# 2_BLE-T1-matrix.net
KiCad netlist of a schematic drawn in Altium Designer
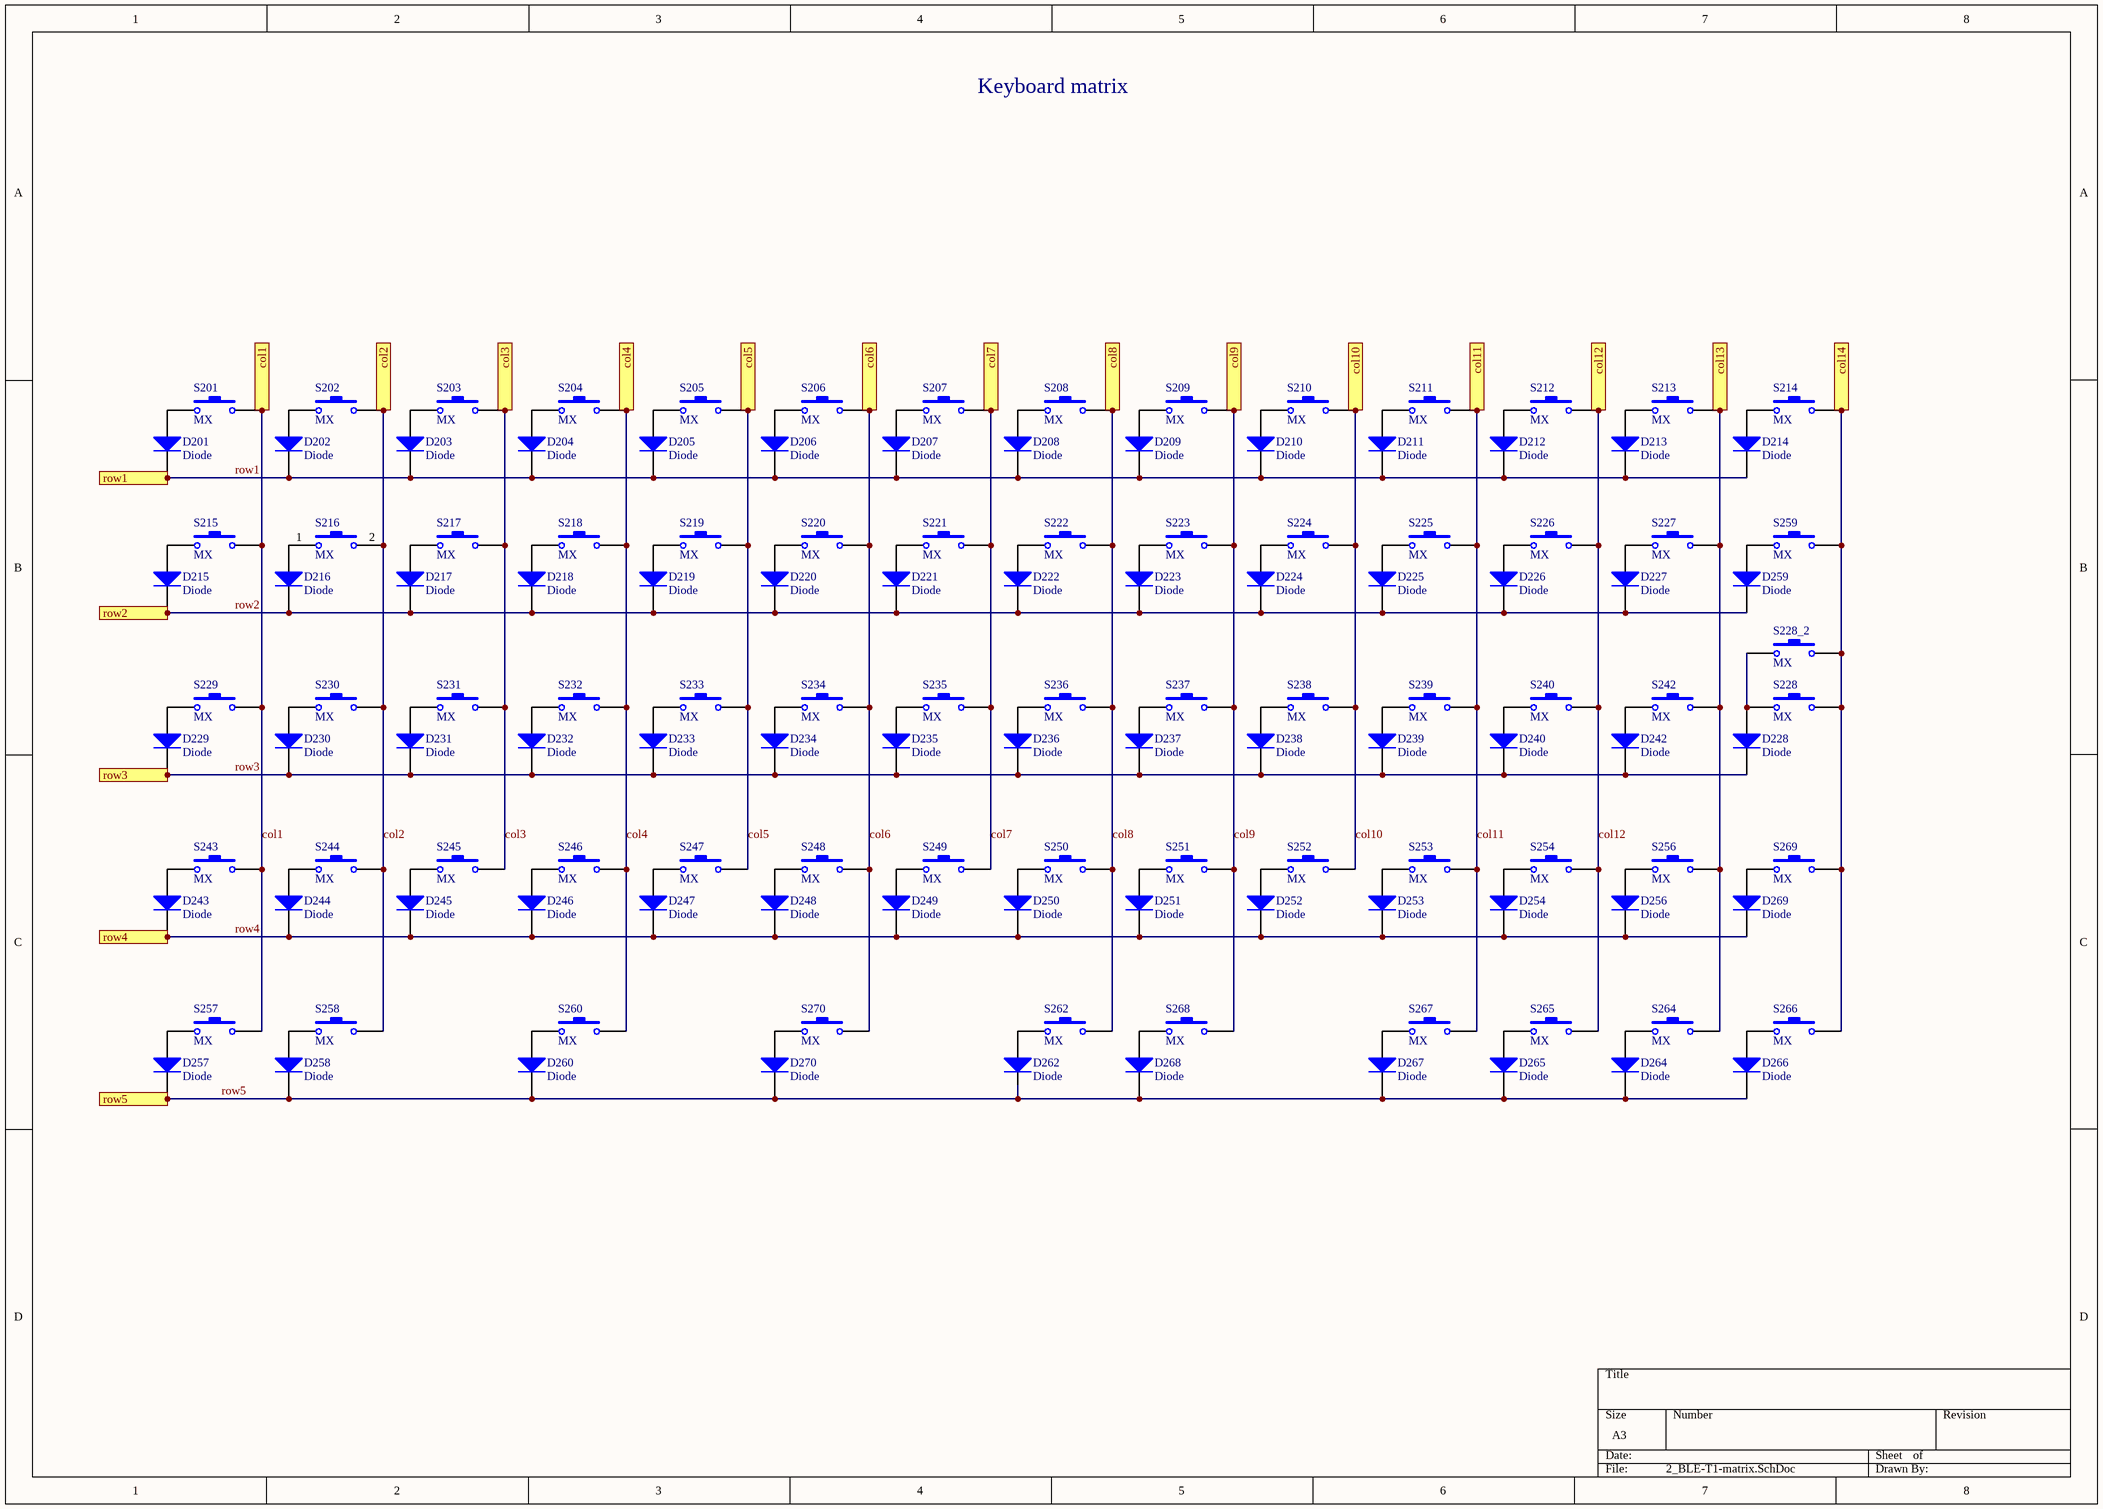
[diagram p0: 2_BLE-T1-matrix.SchDoc]

(export (version "E")
  (design (tool "Eeschema 10.0.6"))
  (components
    (comp (ref "D201")
      (value "Diode")
      (footprint "SOD-123")
      (description "Default Diode")
      (fields (field (name "LCSC PART #") "C81598"))
      (libsource (lib "Miscellaneous Devices") (part "Diode"))
    )
    (comp (ref "D202")
      (value "Diode")
      (footprint "SOD-123")
      (description "Default Diode")
      (fields (field (name "LCSC PART #") "C81598"))
      (libsource (lib "Miscellaneous Devices") (part "Diode"))
    )
    (comp (ref "D203")
      (value "Diode")
      (footprint "SOD-123")
      (description "Default Diode")
      (fields (field (name "LCSC PART #") "C81598"))
      (libsource (lib "Miscellaneous Devices") (part "Diode"))
    )
    (comp (ref "D204")
      (value "Diode")
      (footprint "SOD-123")
      (description "Default Diode")
      (fields (field (name "LCSC PART #") "C81598"))
      (libsource (lib "Miscellaneous Devices") (part "Diode"))
    )
    (comp (ref "D205")
      (value "Diode")
      (footprint "SOD-123")
      (description "Default Diode")
      (fields (field (name "LCSC PART #") "C81598"))
      (libsource (lib "Miscellaneous Devices") (part "Diode"))
    )
    (comp (ref "D206")
      (value "Diode")
      (footprint "SOD-123")
      (description "Default Diode")
      (fields (field (name "LCSC PART #") "C81598"))
      (libsource (lib "Miscellaneous Devices") (part "Diode"))
    )
    (comp (ref "D207")
      (value "Diode")
      (footprint "SOD-123")
      (description "Default Diode")
      (fields (field (name "LCSC PART #") "C81598"))
      (libsource (lib "Miscellaneous Devices") (part "Diode"))
    )
    (comp (ref "D208")
      (value "Diode")
      (footprint "SOD-123")
      (description "Default Diode")
      (fields (field (name "LCSC PART #") "C81598"))
      (libsource (lib "Miscellaneous Devices") (part "Diode"))
    )
    (comp (ref "D209")
      (value "Diode")
      (footprint "SOD-123")
      (description "Default Diode")
      (fields (field (name "LCSC PART #") "C81598"))
      (libsource (lib "Miscellaneous Devices") (part "Diode"))
    )
    (comp (ref "D210")
      (value "Diode")
      (footprint "SOD-123")
      (description "Default Diode")
      (fields (field (name "LCSC PART #") "C81598"))
      (libsource (lib "Miscellaneous Devices") (part "Diode"))
    )
    (comp (ref "D211")
      (value "Diode")
      (footprint "SOD-123")
      (description "Default Diode")
      (fields (field (name "LCSC PART #") "C81598"))
      (libsource (lib "Miscellaneous Devices") (part "Diode"))
    )
    (comp (ref "D212")
      (value "Diode")
      (footprint "SOD-123")
      (description "Default Diode")
      (fields (field (name "LCSC PART #") "C81598"))
      (libsource (lib "Miscellaneous Devices") (part "Diode"))
    )
    (comp (ref "D213")
      (value "Diode")
      (footprint "SOD-123")
      (description "Default Diode")
      (fields (field (name "LCSC PART #") "C81598"))
      (libsource (lib "Miscellaneous Devices") (part "Diode"))
    )
    (comp (ref "D214")
      (value "Diode")
      (footprint "SOD-123")
      (description "Default Diode")
      (fields (field (name "LCSC PART #") "C81598"))
      (libsource (lib "Miscellaneous Devices") (part "Diode"))
    )
    (comp (ref "D215")
      (value "Diode")
      (footprint "SOD-123")
      (description "Default Diode")
      (fields (field (name "LCSC PART #") "C81598"))
      (libsource (lib "Miscellaneous Devices") (part "Diode"))
    )
    (comp (ref "D216")
      (value "Diode")
      (footprint "SOD-123")
      (description "Default Diode")
      (fields (field (name "LCSC PART #") "C81598"))
      (libsource (lib "Miscellaneous Devices") (part "Diode"))
    )
    (comp (ref "D217")
      (value "Diode")
      (footprint "SOD-123")
      (description "Default Diode")
      (fields (field (name "LCSC PART #") "C81598"))
      (libsource (lib "Miscellaneous Devices") (part "Diode"))
    )
    (comp (ref "D218")
      (value "Diode")
      (footprint "SOD-123")
      (description "Default Diode")
      (fields (field (name "LCSC PART #") "C81598"))
      (libsource (lib "Miscellaneous Devices") (part "Diode"))
    )
    (comp (ref "D219")
      (value "Diode")
      (footprint "SOD-123")
      (description "Default Diode")
      (fields (field (name "LCSC PART #") "C81598"))
      (libsource (lib "Miscellaneous Devices") (part "Diode"))
    )
    (comp (ref "D220")
      (value "Diode")
      (footprint "SOD-123")
      (description "Default Diode")
      (fields (field (name "LCSC PART #") "C81598"))
      (libsource (lib "Miscellaneous Devices") (part "Diode"))
    )
    (comp (ref "D221")
      (value "Diode")
      (footprint "SOD-123")
      (description "Default Diode")
      (fields (field (name "LCSC PART #") "C81598"))
      (libsource (lib "Miscellaneous Devices") (part "Diode"))
    )
    (comp (ref "D222")
      (value "Diode")
      (footprint "SOD-123")
      (description "Default Diode")
      (fields (field (name "LCSC PART #") "C81598"))
      (libsource (lib "Miscellaneous Devices") (part "Diode"))
    )
    (comp (ref "D223")
      (value "Diode")
      (footprint "SOD-123")
      (description "Default Diode")
      (fields (field (name "LCSC PART #") "C81598"))
      (libsource (lib "Miscellaneous Devices") (part "Diode"))
    )
    (comp (ref "D224")
      (value "Diode")
      (footprint "SOD-123")
      (description "Default Diode")
      (fields (field (name "LCSC PART #") "C81598"))
      (libsource (lib "Miscellaneous Devices") (part "Diode"))
    )
    (comp (ref "D225")
      (value "Diode")
      (footprint "SOD-123")
      (description "Default Diode")
      (fields (field (name "LCSC PART #") "C81598"))
      (libsource (lib "Miscellaneous Devices") (part "Diode"))
    )
    (comp (ref "D226")
      (value "Diode")
      (footprint "SOD-123")
      (description "Default Diode")
      (fields (field (name "LCSC PART #") "C81598"))
      (libsource (lib "Miscellaneous Devices") (part "Diode"))
    )
    (comp (ref "D227")
      (value "Diode")
      (footprint "SOD-123")
      (description "Default Diode")
      (fields (field (name "LCSC PART #") "C81598"))
      (libsource (lib "Miscellaneous Devices") (part "Diode"))
    )
    (comp (ref "D228")
      (value "Diode")
      (footprint "SOD-123")
      (description "Default Diode")
      (fields (field (name "LCSC PART #") "C81598"))
      (libsource (lib "Miscellaneous Devices") (part "Diode"))
    )
    (comp (ref "D229")
      (value "Diode")
      (footprint "SOD-123")
      (description "Default Diode")
      (fields (field (name "LCSC PART #") "C81598"))
      (libsource (lib "Miscellaneous Devices") (part "Diode"))
    )
    (comp (ref "D230")
      (value "Diode")
      (footprint "SOD-123")
      (description "Default Diode")
      (fields (field (name "LCSC PART #") "C81598"))
      (libsource (lib "Miscellaneous Devices") (part "Diode"))
    )
    (comp (ref "D231")
      (value "Diode")
      (footprint "SOD-123")
      (description "Default Diode")
      (fields (field (name "LCSC PART #") "C81598"))
      (libsource (lib "Miscellaneous Devices") (part "Diode"))
    )
    (comp (ref "D232")
      (value "Diode")
      (footprint "SOD-123")
      (description "Default Diode")
      (fields (field (name "LCSC PART #") "C81598"))
      (libsource (lib "Miscellaneous Devices") (part "Diode"))
    )
    (comp (ref "D233")
      (value "Diode")
      (footprint "SOD-123")
      (description "Default Diode")
      (fields (field (name "LCSC PART #") "C81598"))
      (libsource (lib "Miscellaneous Devices") (part "Diode"))
    )
    (comp (ref "D234")
      (value "Diode")
      (footprint "SOD-123")
      (description "Default Diode")
      (fields (field (name "LCSC PART #") "C81598"))
      (libsource (lib "Miscellaneous Devices") (part "Diode"))
    )
    (comp (ref "D235")
      (value "Diode")
      (footprint "SOD-123")
      (description "Default Diode")
      (fields (field (name "LCSC PART #") "C81598"))
      (libsource (lib "Miscellaneous Devices") (part "Diode"))
    )
    (comp (ref "D236")
      (value "Diode")
      (footprint "SOD-123")
      (description "Default Diode")
      (fields (field (name "LCSC PART #") "C81598"))
      (libsource (lib "Miscellaneous Devices") (part "Diode"))
    )
    (comp (ref "D237")
      (value "Diode")
      (footprint "SOD-123")
      (description "Default Diode")
      (fields (field (name "LCSC PART #") "C81598"))
      (libsource (lib "Miscellaneous Devices") (part "Diode"))
    )
    (comp (ref "D238")
      (value "Diode")
      (footprint "SOD-123")
      (description "Default Diode")
      (fields (field (name "LCSC PART #") "C81598"))
      (libsource (lib "Miscellaneous Devices") (part "Diode"))
    )
    (comp (ref "D239")
      (value "Diode")
      (footprint "SOD-123")
      (description "Default Diode")
      (fields (field (name "LCSC PART #") "C81598"))
      (libsource (lib "Miscellaneous Devices") (part "Diode"))
    )
    (comp (ref "D240")
      (value "Diode")
      (footprint "SOD-123")
      (description "Default Diode")
      (fields (field (name "LCSC PART #") "C81598"))
      (libsource (lib "Miscellaneous Devices") (part "Diode"))
    )
    (comp (ref "D242")
      (value "Diode")
      (footprint "SOD-123")
      (description "Default Diode")
      (fields (field (name "LCSC PART #") "C81598"))
      (libsource (lib "Miscellaneous Devices") (part "Diode"))
    )
    (comp (ref "D243")
      (value "Diode")
      (footprint "SOD-123")
      (description "Default Diode")
      (fields (field (name "LCSC PART #") "C81598"))
      (libsource (lib "Miscellaneous Devices") (part "Diode"))
    )
    (comp (ref "D244")
      (value "Diode")
      (footprint "SOD-123")
      (description "Default Diode")
      (fields (field (name "LCSC PART #") "C81598"))
      (libsource (lib "Miscellaneous Devices") (part "Diode"))
    )
    (comp (ref "D245")
      (value "Diode")
      (footprint "SOD-123")
      (description "Default Diode")
      (fields (field (name "LCSC PART #") "C81598"))
      (libsource (lib "Miscellaneous Devices") (part "Diode"))
    )
    (comp (ref "D246")
      (value "Diode")
      (footprint "SOD-123")
      (description "Default Diode")
      (fields (field (name "LCSC PART #") "C81598"))
      (libsource (lib "Miscellaneous Devices") (part "Diode"))
    )
    (comp (ref "D247")
      (value "Diode")
      (footprint "SOD-123")
      (description "Default Diode")
      (fields (field (name "LCSC PART #") "C81598"))
      (libsource (lib "Miscellaneous Devices") (part "Diode"))
    )
    (comp (ref "D248")
      (value "Diode")
      (footprint "SOD-123")
      (description "Default Diode")
      (fields (field (name "LCSC PART #") "C81598"))
      (libsource (lib "Miscellaneous Devices") (part "Diode"))
    )
    (comp (ref "D249")
      (value "Diode")
      (footprint "SOD-123")
      (description "Default Diode")
      (fields (field (name "LCSC PART #") "C81598"))
      (libsource (lib "Miscellaneous Devices") (part "Diode"))
    )
    (comp (ref "D250")
      (value "Diode")
      (footprint "SOD-123")
      (description "Default Diode")
      (fields (field (name "LCSC PART #") "C81598"))
      (libsource (lib "Miscellaneous Devices") (part "Diode"))
    )
    (comp (ref "D251")
      (value "Diode")
      (footprint "SOD-123")
      (description "Default Diode")
      (fields (field (name "LCSC PART #") "C81598"))
      (libsource (lib "Miscellaneous Devices") (part "Diode"))
    )
    (comp (ref "D252")
      (value "Diode")
      (footprint "SOD-123")
      (description "Default Diode")
      (fields (field (name "LCSC PART #") "C81598"))
      (libsource (lib "Miscellaneous Devices") (part "Diode"))
    )
    (comp (ref "D253")
      (value "Diode")
      (footprint "SOD-123")
      (description "Default Diode")
      (fields (field (name "LCSC PART #") "C81598"))
      (libsource (lib "Miscellaneous Devices") (part "Diode"))
    )
    (comp (ref "D254")
      (value "Diode")
      (footprint "SOD-123")
      (description "Default Diode")
      (fields (field (name "LCSC PART #") "C81598"))
      (libsource (lib "Miscellaneous Devices") (part "Diode"))
    )
    (comp (ref "D256")
      (value "Diode")
      (footprint "SOD-123")
      (description "Default Diode")
      (fields (field (name "LCSC PART #") "C81598"))
      (libsource (lib "Miscellaneous Devices") (part "Diode"))
    )
    (comp (ref "D257")
      (value "Diode")
      (footprint "SOD-123")
      (description "Default Diode")
      (fields (field (name "LCSC PART #") "C81598"))
      (libsource (lib "Miscellaneous Devices") (part "Diode"))
    )
    (comp (ref "D258")
      (value "Diode")
      (footprint "SOD-123")
      (description "Default Diode")
      (fields (field (name "LCSC PART #") "C81598"))
      (libsource (lib "Miscellaneous Devices") (part "Diode"))
    )
    (comp (ref "D259")
      (value "Diode")
      (footprint "SOD-123")
      (description "Default Diode")
      (fields (field (name "LCSC PART #") "C81598"))
      (libsource (lib "Miscellaneous Devices") (part "Diode"))
    )
    (comp (ref "D260")
      (value "Diode")
      (footprint "SOD-123")
      (description "Default Diode")
      (fields (field (name "LCSC PART #") "C81598"))
      (libsource (lib "Miscellaneous Devices") (part "Diode"))
    )
    (comp (ref "D262")
      (value "Diode")
      (footprint "SOD-123")
      (description "Default Diode")
      (fields (field (name "LCSC PART #") "C81598"))
      (libsource (lib "Miscellaneous Devices") (part "Diode"))
    )
    (comp (ref "D264")
      (value "Diode")
      (footprint "SOD-123")
      (description "Default Diode")
      (fields (field (name "LCSC PART #") "C81598"))
      (libsource (lib "Miscellaneous Devices") (part "Diode"))
    )
    (comp (ref "D265")
      (value "Diode")
      (footprint "SOD-123")
      (description "Default Diode")
      (fields (field (name "LCSC PART #") "C81598"))
      (libsource (lib "Miscellaneous Devices") (part "Diode"))
    )
    (comp (ref "D266")
      (value "Diode")
      (footprint "SOD-123")
      (description "Default Diode")
      (fields (field (name "LCSC PART #") "C81598"))
      (libsource (lib "Miscellaneous Devices") (part "Diode"))
    )
    (comp (ref "D267")
      (value "Diode")
      (footprint "SOD-123")
      (description "Default Diode")
      (fields (field (name "LCSC PART #") "C81598"))
      (libsource (lib "Miscellaneous Devices") (part "Diode"))
    )
    (comp (ref "D268")
      (value "Diode")
      (footprint "SOD-123")
      (description "Default Diode")
      (fields (field (name "LCSC PART #") "C81598"))
      (libsource (lib "Miscellaneous Devices") (part "Diode"))
    )
    (comp (ref "D269")
      (value "Diode")
      (footprint "SOD-123")
      (description "Default Diode")
      (fields (field (name "LCSC PART #") "C81598"))
      (libsource (lib "Miscellaneous Devices") (part "Diode"))
    )
    (comp (ref "D270")
      (value "Diode")
      (footprint "SOD-123")
      (description "Default Diode")
      (fields (field (name "LCSC PART #") "C81598"))
      (libsource (lib "Miscellaneous Devices") (part "Diode"))
    )
    (comp (ref "S201")
      (value "MX")
      (footprint "MX-switch - switched pol")
      (description "Switch")
      (libsource (lib "Miscellaneous Devices") (part "SW-PB"))
    )
    (comp (ref "S202")
      (value "MX")
      (footprint "MX-switch - switched pol - connector")
      (description "Switch")
      (libsource (lib "Miscellaneous Devices") (part "SW-PB"))
    )
    (comp (ref "S203")
      (value "MX")
      (footprint "MX-switch - switched pol")
      (description "Switch")
      (libsource (lib "Miscellaneous Devices") (part "SW-PB"))
    )
    (comp (ref "S204")
      (value "MX")
      (footprint "MX-switch")
      (description "Switch")
      (libsource (lib "Miscellaneous Devices") (part "SW-PB"))
    )
    (comp (ref "S205")
      (value "MX")
      (footprint "MX-switch - switched pol")
      (description "Switch")
      (libsource (lib "Miscellaneous Devices") (part "SW-PB"))
    )
    (comp (ref "S206")
      (value "MX")
      (footprint "MX-switch - switched pol")
      (description "Switch")
      (libsource (lib "Miscellaneous Devices") (part "SW-PB"))
    )
    (comp (ref "S207")
      (value "MX")
      (footprint "MX-switch - switched pol")
      (description "Switch")
      (libsource (lib "Miscellaneous Devices") (part "SW-PB"))
    )
    (comp (ref "S208")
      (value "MX")
      (footprint "MX-switch - switched pol")
      (description "Switch")
      (libsource (lib "Miscellaneous Devices") (part "SW-PB"))
    )
    (comp (ref "S209")
      (value "MX")
      (footprint "MX-switch - switched pol")
      (description "Switch")
      (libsource (lib "Miscellaneous Devices") (part "SW-PB"))
    )
    (comp (ref "S210")
      (value "MX")
      (footprint "MX-switch - switched pol")
      (description "Switch")
      (libsource (lib "Miscellaneous Devices") (part "SW-PB"))
    )
    (comp (ref "S211")
      (value "MX")
      (footprint "MX-switch - switched pol")
      (description "Switch")
      (libsource (lib "Miscellaneous Devices") (part "SW-PB"))
    )
    (comp (ref "S212")
      (value "MX")
      (footprint "MX-switch - switched pol")
      (description "Switch")
      (libsource (lib "Miscellaneous Devices") (part "SW-PB"))
    )
    (comp (ref "S213")
      (value "MX")
      (footprint "MX-switch")
      (description "Switch")
      (libsource (lib "Miscellaneous Devices") (part "SW-PB"))
    )
    (comp (ref "S214")
      (value "MX")
      (footprint "MX-switch - switched pol")
      (description "Switch")
      (libsource (lib "Miscellaneous Devices") (part "SW-PB"))
    )
    (comp (ref "S215")
      (value "MX")
      (footprint "MX-switch - 1.5U - switched pol")
      (description "TAB")
      (libsource (lib "Miscellaneous Devices") (part "SW-PB"))
    )
    (comp (ref "S216")
      (value "MX")
      (footprint "MX-switch - switched pol")
      (description "Switch")
      (libsource (lib "") (part "SW-PB_1"))
    )
    (comp (ref "S217")
      (value "MX")
      (footprint "MX-switch - switched pol")
      (description "Switch")
      (libsource (lib "Miscellaneous Devices") (part "SW-PB"))
    )
    (comp (ref "S218")
      (value "MX")
      (footprint "MX-switch - switched pol")
      (description "Switch")
      (libsource (lib "Miscellaneous Devices") (part "SW-PB"))
    )
    (comp (ref "S219")
      (value "MX")
      (footprint "MX-switch - switched pol")
      (description "Switch")
      (libsource (lib "Miscellaneous Devices") (part "SW-PB"))
    )
    (comp (ref "S220")
      (value "MX")
      (footprint "MX-switch")
      (description "Switch")
      (libsource (lib "Miscellaneous Devices") (part "SW-PB"))
    )
    (comp (ref "S221")
      (value "MX")
      (footprint "MX-switch - switched pol")
      (description "Switch")
      (libsource (lib "Miscellaneous Devices") (part "SW-PB"))
    )
    (comp (ref "S222")
      (value "MX")
      (footprint "MX-switch - switched pol")
      (description "Switch")
      (libsource (lib "Miscellaneous Devices") (part "SW-PB"))
    )
    (comp (ref "S223")
      (value "MX")
      (footprint "MX-switch - switched pol")
      (description "Switch")
      (libsource (lib "Miscellaneous Devices") (part "SW-PB"))
    )
    (comp (ref "S224")
      (value "MX")
      (footprint "MX-switch - switched pol")
      (description "Switch")
      (libsource (lib "Miscellaneous Devices") (part "SW-PB"))
    )
    (comp (ref "S225")
      (value "MX")
      (footprint "MX-switch - switched pol")
      (description "Switch")
      (libsource (lib "Miscellaneous Devices") (part "SW-PB"))
    )
    (comp (ref "S226")
      (value "MX")
      (footprint "MX-switch")
      (description "Switch")
      (libsource (lib "Miscellaneous Devices") (part "SW-PB"))
    )
    (comp (ref "S227")
      (value "MX")
      (footprint "MX-switch")
      (description "Switch")
      (libsource (lib "Miscellaneous Devices") (part "SW-PB"))
    )
    (comp (ref "S228")
      (value "MX")
      (footprint "MX-switch - 1.5U")
      (description "Switch")
      (libsource (lib "Miscellaneous Devices") (part "SW-PB"))
    )
    (comp (ref "S228_2")
      (value "MX")
      (footprint "MX-switch")
      (description "Switch")
      (libsource (lib "Miscellaneous Devices") (part "SW-PB"))
    )
    (comp (ref "S229")
      (value "MX")
      (footprint "MX-switch - CAPS")
      (description "Switch")
      (libsource (lib "Miscellaneous Devices") (part "SW-PB"))
    )
    (comp (ref "S230")
      (value "MX")
      (footprint "MX-switch - switched pol")
      (description "Switch")
      (libsource (lib "Miscellaneous Devices") (part "SW-PB"))
    )
    (comp (ref "S231")
      (value "MX")
      (footprint "MX-switch - switched pol")
      (description "Switch")
      (libsource (lib "Miscellaneous Devices") (part "SW-PB"))
    )
    (comp (ref "S232")
      (value "MX")
      (footprint "MX-switch - switched pol")
      (description "Switch")
      (libsource (lib "Miscellaneous Devices") (part "SW-PB"))
    )
    (comp (ref "S233")
      (value "MX")
      (footprint "MX-switch - switched pol")
      (description "Switch")
      (libsource (lib "Miscellaneous Devices") (part "SW-PB"))
    )
    (comp (ref "S234")
      (value "MX")
      (footprint "MX-switch")
      (description "Switch")
      (libsource (lib "Miscellaneous Devices") (part "SW-PB"))
    )
    (comp (ref "S235")
      (value "MX")
      (footprint "MX-switch - switched pol")
      (description "Switch")
      (libsource (lib "Miscellaneous Devices") (part "SW-PB"))
    )
    (comp (ref "S236")
      (value "MX")
      (footprint "MX-switch - switched pol")
      (description "Switch")
      (libsource (lib "Miscellaneous Devices") (part "SW-PB"))
    )
    (comp (ref "S237")
      (value "MX")
      (footprint "MX-switch - switched pol")
      (description "Switch")
      (libsource (lib "Miscellaneous Devices") (part "SW-PB"))
    )
    (comp (ref "S238")
      (value "MX")
      (footprint "MX-switch - switched pol")
      (description "Switch")
      (libsource (lib "Miscellaneous Devices") (part "SW-PB"))
    )
    (comp (ref "S239")
      (value "MX")
      (footprint "MX-switch")
      (description "Switch")
      (libsource (lib "Miscellaneous Devices") (part "SW-PB"))
    )
    (comp (ref "S240")
      (value "MX")
      (footprint "MX-switch - switched pol")
      (description "Switch")
      (libsource (lib "Miscellaneous Devices") (part "SW-PB"))
    )
    (comp (ref "S242")
      (value "MX")
      (footprint "MX-switch - Enter")
      (description "Switch")
      (libsource (lib "Miscellaneous Devices") (part "SW-PB"))
    )
    (comp (ref "S243")
      (value "MX")
      (footprint "MX-switch - Left shift")
      (description "Switch")
      (libsource (lib "Miscellaneous Devices") (part "SW-PB"))
    )
    (comp (ref "S244")
      (value "MX")
      (footprint "MX-switch - switched pol")
      (description "Switch")
      (libsource (lib "Miscellaneous Devices") (part "SW-PB"))
    )
    (comp (ref "S245")
      (value "MX")
      (footprint "MX-switch - switched pol")
      (description "Switch")
      (libsource (lib "Miscellaneous Devices") (part "SW-PB"))
    )
    (comp (ref "S246")
      (value "MX")
      (footprint "MX-switch - switched pol")
      (description "Switch")
      (libsource (lib "Miscellaneous Devices") (part "SW-PB"))
    )
    (comp (ref "S247")
      (value "MX")
      (footprint "MX-switch - switched pol")
      (description "Switch")
      (libsource (lib "Miscellaneous Devices") (part "SW-PB"))
    )
    (comp (ref "S248")
      (value "MX")
      (footprint "MX-switch - switched pol")
      (description "Switch")
      (libsource (lib "Miscellaneous Devices") (part "SW-PB"))
    )
    (comp (ref "S249")
      (value "MX")
      (footprint "MX-switch - switched pol")
      (description "Switch")
      (libsource (lib "Miscellaneous Devices") (part "SW-PB"))
    )
    (comp (ref "S250")
      (value "MX")
      (footprint "MX-switch - switched pol")
      (description "Switch")
      (libsource (lib "Miscellaneous Devices") (part "SW-PB"))
    )
    (comp (ref "S251")
      (value "MX")
      (footprint "MX-switch - switched pol")
      (description "Switch")
      (libsource (lib "Miscellaneous Devices") (part "SW-PB"))
    )
    (comp (ref "S252")
      (value "MX")
      (footprint "MX-switch - switched pol")
      (description "Switch")
      (libsource (lib "Miscellaneous Devices") (part "SW-PB"))
    )
    (comp (ref "S253")
      (value "MX")
      (footprint "MX-switch - switched pol")
      (description "Switch")
      (libsource (lib "Miscellaneous Devices") (part "SW-PB"))
    )
    (comp (ref "S254")
      (value "MX")
      (footprint "MX-switch - switched pol")
      (description "Switch")
      (libsource (lib "Miscellaneous Devices") (part "SW-PB"))
    )
    (comp (ref "S256")
      (value "MX")
      (footprint "MX-switch - right shift")
      (description "Switch")
      (libsource (lib "Miscellaneous Devices") (part "SW-PB"))
    )
    (comp (ref "S257")
      (value "MX")
      (footprint "MX-switch - 1.5u MOD-L")
      (description "Switch")
      (libsource (lib "Miscellaneous Devices") (part "SW-PB"))
    )
    (comp (ref "S258")
      (value "MX")
      (footprint "MX-switch - 1u MOD-L")
      (description "Switch")
      (libsource (lib "Miscellaneous Devices") (part "SW-PB"))
    )
    (comp (ref "S259")
      (value "MX")
      (footprint "MX-switch - backspace")
      (description "Switch")
      (libsource (lib "Miscellaneous Devices") (part "SW-PB"))
    )
    (comp (ref "S260")
      (value "MX")
      (footprint "MX-switch - 1.5u MOD-L")
      (description "Switch")
      (libsource (lib "Miscellaneous Devices") (part "SW-PB"))
    )
    (comp (ref "S262")
      (value "MX")
      (footprint "MX-switch - Space_V3")
      (description "Switch")
      (libsource (lib "Miscellaneous Devices") (part "SW-PB"))
    )
    (comp (ref "S264")
      (value "MX")
      (footprint "MX-switch - 1u MOD-R")
      (description "Switch")
      (libsource (lib "Miscellaneous Devices") (part "SW-PB"))
    )
    (comp (ref "S265")
      (value "MX")
      (footprint "MX-switch - 1.5u MOD-R")
      (description "Switch")
      (libsource (lib "Miscellaneous Devices") (part "SW-PB"))
    )
    (comp (ref "S266")
      (value "MX")
      (footprint "MX-switch - 1.5u MOD-R")
      (description "Switch")
      (libsource (lib "Miscellaneous Devices") (part "SW-PB"))
    )
    (comp (ref "S267")
      (value "MX")
      (footprint "MX-switch - switched pol")
      (description "Switch")
      (libsource (lib "Miscellaneous Devices") (part "SW-PB"))
    )
    (comp (ref "S268")
      (value "MX")
      (footprint "MX-switch - R split space_V2")
      (description "Switch")
      (libsource (lib "Miscellaneous Devices") (part "SW-PB"))
    )
    (comp (ref "S269")
      (value "MX")
      (footprint "MX-switch")
      (description "Switch")
      (libsource (lib "Miscellaneous Devices") (part "SW-PB"))
    )
    (comp (ref "S270")
      (value "MX")
      (footprint "MX-switch - L split space_V2")
      (description "Switch")
      (libsource (lib "Miscellaneous Devices") (part "SW-PB"))
    )
  )
  (nets
    (net (code "1") (name "/col1") (class "Default")
      (node (ref "S201") (pin "2") (pinfunction "2_2") (pintype "passive"))
      (node (ref "S215") (pin "2") (pinfunction "2_2") (pintype "passive"))
      (node (ref "S229") (pin "2") (pinfunction "2_2") (pintype "passive"))
      (node (ref "S243") (pin "2") (pinfunction "2_2") (pintype "passive"))
      (node (ref "S257") (pin "2") (pinfunction "2_2") (pintype "passive"))
    )
    (net (code "2") (name "/col2") (class "Default")
      (node (ref "S202") (pin "2") (pinfunction "2_2") (pintype "passive"))
      (node (ref "S216") (pin "2") (pinfunction "2_2") (pintype "passive"))
      (node (ref "S230") (pin "2") (pinfunction "2_2") (pintype "passive"))
      (node (ref "S244") (pin "2") (pinfunction "2_2") (pintype "passive"))
      (node (ref "S258") (pin "2") (pinfunction "2_2") (pintype "passive"))
    )
    (net (code "3") (name "/col3") (class "Default")
      (node (ref "S203") (pin "2") (pinfunction "2_2") (pintype "passive"))
      (node (ref "S217") (pin "2") (pinfunction "2_2") (pintype "passive"))
      (node (ref "S231") (pin "2") (pinfunction "2_2") (pintype "passive"))
      (node (ref "S245") (pin "2") (pinfunction "2_2") (pintype "passive"))
    )
    (net (code "4") (name "/col4") (class "Default")
      (node (ref "S204") (pin "2") (pinfunction "2_2") (pintype "passive"))
      (node (ref "S218") (pin "2") (pinfunction "2_2") (pintype "passive"))
      (node (ref "S232") (pin "2") (pinfunction "2_2") (pintype "passive"))
      (node (ref "S246") (pin "2") (pinfunction "2_2") (pintype "passive"))
      (node (ref "S260") (pin "2") (pinfunction "2_2") (pintype "passive"))
    )
    (net (code "5") (name "/col5") (class "Default")
      (node (ref "S205") (pin "2") (pinfunction "2_2") (pintype "passive"))
      (node (ref "S219") (pin "2") (pinfunction "2_2") (pintype "passive"))
      (node (ref "S233") (pin "2") (pinfunction "2_2") (pintype "passive"))
      (node (ref "S247") (pin "2") (pinfunction "2_2") (pintype "passive"))
    )
    (net (code "6") (name "/col6") (class "Default")
      (node (ref "S206") (pin "2") (pinfunction "2_2") (pintype "passive"))
      (node (ref "S220") (pin "2") (pinfunction "2_2") (pintype "passive"))
      (node (ref "S234") (pin "2") (pinfunction "2_2") (pintype "passive"))
      (node (ref "S248") (pin "2") (pinfunction "2_2") (pintype "passive"))
      (node (ref "S270") (pin "2") (pinfunction "2_2") (pintype "passive"))
    )
    (net (code "7") (name "/col7") (class "Default")
      (node (ref "S207") (pin "2") (pinfunction "2_2") (pintype "passive"))
      (node (ref "S221") (pin "2") (pinfunction "2_2") (pintype "passive"))
      (node (ref "S235") (pin "2") (pinfunction "2_2") (pintype "passive"))
      (node (ref "S249") (pin "2") (pinfunction "2_2") (pintype "passive"))
    )
    (net (code "8") (name "/col8") (class "Default")
      (node (ref "S208") (pin "2") (pinfunction "2_2") (pintype "passive"))
      (node (ref "S222") (pin "2") (pinfunction "2_2") (pintype "passive"))
      (node (ref "S236") (pin "2") (pinfunction "2_2") (pintype "passive"))
      (node (ref "S250") (pin "2") (pinfunction "2_2") (pintype "passive"))
      (node (ref "S262") (pin "2") (pinfunction "2_2") (pintype "passive"))
    )
    (net (code "9") (name "/col9") (class "Default")
      (node (ref "S209") (pin "2") (pinfunction "2_2") (pintype "passive"))
      (node (ref "S223") (pin "2") (pinfunction "2_2") (pintype "passive"))
      (node (ref "S237") (pin "2") (pinfunction "2_2") (pintype "passive"))
      (node (ref "S251") (pin "2") (pinfunction "2_2") (pintype "passive"))
      (node (ref "S268") (pin "2") (pinfunction "2_2") (pintype "passive"))
    )
    (net (code "10") (name "/col10") (class "Default")
      (node (ref "S210") (pin "2") (pinfunction "2_2") (pintype "passive"))
      (node (ref "S224") (pin "2") (pinfunction "2_2") (pintype "passive"))
      (node (ref "S238") (pin "2") (pinfunction "2_2") (pintype "passive"))
      (node (ref "S252") (pin "2") (pinfunction "2_2") (pintype "passive"))
    )
    (net (code "11") (name "/col11") (class "Default")
      (node (ref "S211") (pin "2") (pinfunction "2_2") (pintype "passive"))
      (node (ref "S225") (pin "2") (pinfunction "2_2") (pintype "passive"))
      (node (ref "S239") (pin "2") (pinfunction "2_2") (pintype "passive"))
      (node (ref "S253") (pin "2") (pinfunction "2_2") (pintype "passive"))
      (node (ref "S267") (pin "2") (pinfunction "2_2") (pintype "passive"))
    )
    (net (code "12") (name "/col12") (class "Default")
      (node (ref "S212") (pin "2") (pinfunction "2_2") (pintype "passive"))
      (node (ref "S226") (pin "2") (pinfunction "2_2") (pintype "passive"))
      (node (ref "S240") (pin "2") (pinfunction "2_2") (pintype "passive"))
      (node (ref "S254") (pin "2") (pinfunction "2_2") (pintype "passive"))
      (node (ref "S265") (pin "2") (pinfunction "2_2") (pintype "passive"))
    )
    (net (code "13") (name "/col13") (class "Default")
      (node (ref "S213") (pin "2") (pinfunction "2_2") (pintype "passive"))
      (node (ref "S227") (pin "2") (pinfunction "2_2") (pintype "passive"))
      (node (ref "S242") (pin "2") (pinfunction "2_2") (pintype "passive"))
      (node (ref "S256") (pin "2") (pinfunction "2_2") (pintype "passive"))
      (node (ref "S264") (pin "2") (pinfunction "2_2") (pintype "passive"))
    )
    (net (code "14") (name "/col14") (class "Default")
      (node (ref "S214") (pin "2") (pinfunction "2_2") (pintype "passive"))
      (node (ref "S228") (pin "2") (pinfunction "2_2") (pintype "passive"))
      (node (ref "S228_2") (pin "2") (pinfunction "2_2") (pintype "passive"))
      (node (ref "S259") (pin "2") (pinfunction "2_2") (pintype "passive"))
      (node (ref "S266") (pin "2") (pinfunction "2_2") (pintype "passive"))
      (node (ref "S269") (pin "2") (pinfunction "2_2") (pintype "passive"))
    )
    (net (code "15") (name "/row1") (class "Default")
      (node (ref "D201") (pin "2") (pinfunction "K_2") (pintype "passive"))
      (node (ref "D202") (pin "2") (pinfunction "K_2") (pintype "passive"))
      (node (ref "D203") (pin "2") (pinfunction "K_2") (pintype "passive"))
      (node (ref "D204") (pin "2") (pinfunction "K_2") (pintype "passive"))
      (node (ref "D205") (pin "2") (pinfunction "K_2") (pintype "passive"))
      (node (ref "D206") (pin "2") (pinfunction "K_2") (pintype "passive"))
      (node (ref "D207") (pin "2") (pinfunction "K_2") (pintype "passive"))
      (node (ref "D208") (pin "2") (pinfunction "K_2") (pintype "passive"))
      (node (ref "D209") (pin "2") (pinfunction "K_2") (pintype "passive"))
      (node (ref "D210") (pin "2") (pinfunction "K_2") (pintype "passive"))
      (node (ref "D211") (pin "2") (pinfunction "K_2") (pintype "passive"))
      (node (ref "D212") (pin "2") (pinfunction "K_2") (pintype "passive"))
      (node (ref "D213") (pin "2") (pinfunction "K_2") (pintype "passive"))
      (node (ref "D214") (pin "2") (pinfunction "K_2") (pintype "passive"))
    )
    (net (code "16") (name "/row2") (class "Default")
      (node (ref "D215") (pin "2") (pinfunction "K_2") (pintype "passive"))
      (node (ref "D216") (pin "2") (pinfunction "K_2") (pintype "passive"))
      (node (ref "D217") (pin "2") (pinfunction "K_2") (pintype "passive"))
      (node (ref "D218") (pin "2") (pinfunction "K_2") (pintype "passive"))
      (node (ref "D219") (pin "2") (pinfunction "K_2") (pintype "passive"))
      (node (ref "D220") (pin "2") (pinfunction "K_2") (pintype "passive"))
      (node (ref "D221") (pin "2") (pinfunction "K_2") (pintype "passive"))
      (node (ref "D222") (pin "2") (pinfunction "K_2") (pintype "passive"))
      (node (ref "D223") (pin "2") (pinfunction "K_2") (pintype "passive"))
      (node (ref "D224") (pin "2") (pinfunction "K_2") (pintype "passive"))
      (node (ref "D225") (pin "2") (pinfunction "K_2") (pintype "passive"))
      (node (ref "D226") (pin "2") (pinfunction "K_2") (pintype "passive"))
      (node (ref "D227") (pin "2") (pinfunction "K_2") (pintype "passive"))
      (node (ref "D259") (pin "2") (pinfunction "K_2") (pintype "passive"))
    )
    (net (code "17") (name "/row3") (class "Default")
      (node (ref "D228") (pin "2") (pinfunction "K_2") (pintype "passive"))
      (node (ref "D229") (pin "2") (pinfunction "K_2") (pintype "passive"))
      (node (ref "D230") (pin "2") (pinfunction "K_2") (pintype "passive"))
      (node (ref "D231") (pin "2") (pinfunction "K_2") (pintype "passive"))
      (node (ref "D232") (pin "2") (pinfunction "K_2") (pintype "passive"))
      (node (ref "D233") (pin "2") (pinfunction "K_2") (pintype "passive"))
      (node (ref "D234") (pin "2") (pinfunction "K_2") (pintype "passive"))
      (node (ref "D235") (pin "2") (pinfunction "K_2") (pintype "passive"))
      (node (ref "D236") (pin "2") (pinfunction "K_2") (pintype "passive"))
      (node (ref "D237") (pin "2") (pinfunction "K_2") (pintype "passive"))
      (node (ref "D238") (pin "2") (pinfunction "K_2") (pintype "passive"))
      (node (ref "D239") (pin "2") (pinfunction "K_2") (pintype "passive"))
      (node (ref "D240") (pin "2") (pinfunction "K_2") (pintype "passive"))
      (node (ref "D242") (pin "2") (pinfunction "K_2") (pintype "passive"))
    )
    (net (code "18") (name "/row4") (class "Default")
      (node (ref "D243") (pin "2") (pinfunction "K_2") (pintype "passive"))
      (node (ref "D244") (pin "2") (pinfunction "K_2") (pintype "passive"))
      (node (ref "D245") (pin "2") (pinfunction "K_2") (pintype "passive"))
      (node (ref "D246") (pin "2") (pinfunction "K_2") (pintype "passive"))
      (node (ref "D247") (pin "2") (pinfunction "K_2") (pintype "passive"))
      (node (ref "D248") (pin "2") (pinfunction "K_2") (pintype "passive"))
      (node (ref "D249") (pin "2") (pinfunction "K_2") (pintype "passive"))
      (node (ref "D250") (pin "2") (pinfunction "K_2") (pintype "passive"))
      (node (ref "D251") (pin "2") (pinfunction "K_2") (pintype "passive"))
      (node (ref "D252") (pin "2") (pinfunction "K_2") (pintype "passive"))
      (node (ref "D253") (pin "2") (pinfunction "K_2") (pintype "passive"))
      (node (ref "D254") (pin "2") (pinfunction "K_2") (pintype "passive"))
      (node (ref "D256") (pin "2") (pinfunction "K_2") (pintype "passive"))
      (node (ref "D269") (pin "2") (pinfunction "K_2") (pintype "passive"))
    )
    (net (code "19") (name "/row5") (class "Default")
      (node (ref "D257") (pin "2") (pinfunction "K_2") (pintype "passive"))
      (node (ref "D258") (pin "2") (pinfunction "K_2") (pintype "passive"))
      (node (ref "D260") (pin "2") (pinfunction "K_2") (pintype "passive"))
      (node (ref "D262") (pin "2") (pinfunction "K_2") (pintype "passive"))
      (node (ref "D264") (pin "2") (pinfunction "K_2") (pintype "passive"))
      (node (ref "D265") (pin "2") (pinfunction "K_2") (pintype "passive"))
      (node (ref "D266") (pin "2") (pinfunction "K_2") (pintype "passive"))
      (node (ref "D267") (pin "2") (pinfunction "K_2") (pintype "passive"))
      (node (ref "D268") (pin "2") (pinfunction "K_2") (pintype "passive"))
      (node (ref "D270") (pin "2") (pinfunction "K_2") (pintype "passive"))
    )
    (net (code "20") (name "Net-(D201-A)") (class "Default")
      (node (ref "D201") (pin "1") (pinfunction "A_1") (pintype "passive"))
      (node (ref "S201") (pin "1") (pinfunction "1_1") (pintype "passive"))
    )
    (net (code "21") (name "Net-(D202-A)") (class "Default")
      (node (ref "D202") (pin "1") (pinfunction "A_1") (pintype "passive"))
      (node (ref "S202") (pin "1") (pinfunction "1_1") (pintype "passive"))
    )
    (net (code "22") (name "Net-(D203-A)") (class "Default")
      (node (ref "D203") (pin "1") (pinfunction "A_1") (pintype "passive"))
      (node (ref "S203") (pin "1") (pinfunction "1_1") (pintype "passive"))
    )
    (net (code "23") (name "Net-(D204-A)") (class "Default")
      (node (ref "D204") (pin "1") (pinfunction "A_1") (pintype "passive"))
      (node (ref "S204") (pin "1") (pinfunction "1_1") (pintype "passive"))
    )
    (net (code "24") (name "Net-(D205-A)") (class "Default")
      (node (ref "D205") (pin "1") (pinfunction "A_1") (pintype "passive"))
      (node (ref "S205") (pin "1") (pinfunction "1_1") (pintype "passive"))
    )
    (net (code "25") (name "Net-(D206-A)") (class "Default")
      (node (ref "D206") (pin "1") (pinfunction "A_1") (pintype "passive"))
      (node (ref "S206") (pin "1") (pinfunction "1_1") (pintype "passive"))
    )
    (net (code "26") (name "Net-(D207-A)") (class "Default")
      (node (ref "D207") (pin "1") (pinfunction "A_1") (pintype "passive"))
      (node (ref "S207") (pin "1") (pinfunction "1_1") (pintype "passive"))
    )
    (net (code "27") (name "Net-(D208-A)") (class "Default")
      (node (ref "D208") (pin "1") (pinfunction "A_1") (pintype "passive"))
      (node (ref "S208") (pin "1") (pinfunction "1_1") (pintype "passive"))
    )
    (net (code "28") (name "Net-(D209-A)") (class "Default")
      (node (ref "D209") (pin "1") (pinfunction "A_1") (pintype "passive"))
      (node (ref "S209") (pin "1") (pinfunction "1_1") (pintype "passive"))
    )
    (net (code "29") (name "Net-(D210-A)") (class "Default")
      (node (ref "D210") (pin "1") (pinfunction "A_1") (pintype "passive"))
      (node (ref "S210") (pin "1") (pinfunction "1_1") (pintype "passive"))
    )
    (net (code "30") (name "Net-(D211-A)") (class "Default")
      (node (ref "D211") (pin "1") (pinfunction "A_1") (pintype "passive"))
      (node (ref "S211") (pin "1") (pinfunction "1_1") (pintype "passive"))
    )
    (net (code "31") (name "Net-(D212-A)") (class "Default")
      (node (ref "D212") (pin "1") (pinfunction "A_1") (pintype "passive"))
      (node (ref "S212") (pin "1") (pinfunction "1_1") (pintype "passive"))
    )
    (net (code "32") (name "Net-(D213-A)") (class "Default")
      (node (ref "D213") (pin "1") (pinfunction "A_1") (pintype "passive"))
      (node (ref "S213") (pin "1") (pinfunction "1_1") (pintype "passive"))
    )
    (net (code "33") (name "Net-(D214-A)") (class "Default")
      (node (ref "D214") (pin "1") (pinfunction "A_1") (pintype "passive"))
      (node (ref "S214") (pin "1") (pinfunction "1_1") (pintype "passive"))
    )
    (net (code "34") (name "Net-(D215-A)") (class "Default")
      (node (ref "D215") (pin "1") (pinfunction "A_1") (pintype "passive"))
      (node (ref "S215") (pin "1") (pinfunction "1_1") (pintype "passive"))
    )
    (net (code "35") (name "Net-(D216-A)") (class "Default")
      (node (ref "D216") (pin "1") (pinfunction "A_1") (pintype "passive"))
      (node (ref "S216") (pin "1") (pinfunction "1_1") (pintype "passive"))
    )
    (net (code "36") (name "Net-(D217-A)") (class "Default")
      (node (ref "D217") (pin "1") (pinfunction "A_1") (pintype "passive"))
      (node (ref "S217") (pin "1") (pinfunction "1_1") (pintype "passive"))
    )
    (net (code "37") (name "Net-(D218-A)") (class "Default")
      (node (ref "D218") (pin "1") (pinfunction "A_1") (pintype "passive"))
      (node (ref "S218") (pin "1") (pinfunction "1_1") (pintype "passive"))
    )
    (net (code "38") (name "Net-(D219-A)") (class "Default")
      (node (ref "D219") (pin "1") (pinfunction "A_1") (pintype "passive"))
      (node (ref "S219") (pin "1") (pinfunction "1_1") (pintype "passive"))
    )
    (net (code "39") (name "Net-(D220-A)") (class "Default")
      (node (ref "D220") (pin "1") (pinfunction "A_1") (pintype "passive"))
      (node (ref "S220") (pin "1") (pinfunction "1_1") (pintype "passive"))
    )
    (net (code "40") (name "Net-(D221-A)") (class "Default")
      (node (ref "D221") (pin "1") (pinfunction "A_1") (pintype "passive"))
      (node (ref "S221") (pin "1") (pinfunction "1_1") (pintype "passive"))
    )
    (net (code "41") (name "Net-(D222-A)") (class "Default")
      (node (ref "D222") (pin "1") (pinfunction "A_1") (pintype "passive"))
      (node (ref "S222") (pin "1") (pinfunction "1_1") (pintype "passive"))
    )
    (net (code "42") (name "Net-(D223-A)") (class "Default")
      (node (ref "D223") (pin "1") (pinfunction "A_1") (pintype "passive"))
      (node (ref "S223") (pin "1") (pinfunction "1_1") (pintype "passive"))
    )
    (net (code "43") (name "Net-(D224-A)") (class "Default")
      (node (ref "D224") (pin "1") (pinfunction "A_1") (pintype "passive"))
      (node (ref "S224") (pin "1") (pinfunction "1_1") (pintype "passive"))
    )
    (net (code "44") (name "Net-(D225-A)") (class "Default")
      (node (ref "D225") (pin "1") (pinfunction "A_1") (pintype "passive"))
      (node (ref "S225") (pin "1") (pinfunction "1_1") (pintype "passive"))
    )
    (net (code "45") (name "Net-(D226-A)") (class "Default")
      (node (ref "D226") (pin "1") (pinfunction "A_1") (pintype "passive"))
      (node (ref "S226") (pin "1") (pinfunction "1_1") (pintype "passive"))
    )
    (net (code "46") (name "Net-(D227-A)") (class "Default")
      (node (ref "D227") (pin "1") (pinfunction "A_1") (pintype "passive"))
      (node (ref "S227") (pin "1") (pinfunction "1_1") (pintype "passive"))
    )
    (net (code "47") (name "Net-(D228-A)") (class "Default")
      (node (ref "D228") (pin "1") (pinfunction "A_1") (pintype "passive"))
      (node (ref "S228") (pin "1") (pinfunction "1_1") (pintype "passive"))
      (node (ref "S228_2") (pin "1") (pinfunction "1_1") (pintype "passive"))
    )
    (net (code "48") (name "Net-(D229-A)") (class "Default")
      (node (ref "D229") (pin "1") (pinfunction "A_1") (pintype "passive"))
      (node (ref "S229") (pin "1") (pinfunction "1_1") (pintype "passive"))
    )
    (net (code "49") (name "Net-(D230-A)") (class "Default")
      (node (ref "D230") (pin "1") (pinfunction "A_1") (pintype "passive"))
      (node (ref "S230") (pin "1") (pinfunction "1_1") (pintype "passive"))
    )
    (net (code "50") (name "Net-(D231-A)") (class "Default")
      (node (ref "D231") (pin "1") (pinfunction "A_1") (pintype "passive"))
      (node (ref "S231") (pin "1") (pinfunction "1_1") (pintype "passive"))
    )
    (net (code "51") (name "Net-(D232-A)") (class "Default")
      (node (ref "D232") (pin "1") (pinfunction "A_1") (pintype "passive"))
      (node (ref "S232") (pin "1") (pinfunction "1_1") (pintype "passive"))
    )
    (net (code "52") (name "Net-(D233-A)") (class "Default")
      (node (ref "D233") (pin "1") (pinfunction "A_1") (pintype "passive"))
      (node (ref "S233") (pin "1") (pinfunction "1_1") (pintype "passive"))
    )
    (net (code "53") (name "Net-(D234-A)") (class "Default")
      (node (ref "D234") (pin "1") (pinfunction "A_1") (pintype "passive"))
      (node (ref "S234") (pin "1") (pinfunction "1_1") (pintype "passive"))
    )
    (net (code "54") (name "Net-(D235-A)") (class "Default")
      (node (ref "D235") (pin "1") (pinfunction "A_1") (pintype "passive"))
      (node (ref "S235") (pin "1") (pinfunction "1_1") (pintype "passive"))
    )
    (net (code "55") (name "Net-(D236-A)") (class "Default")
      (node (ref "D236") (pin "1") (pinfunction "A_1") (pintype "passive"))
      (node (ref "S236") (pin "1") (pinfunction "1_1") (pintype "passive"))
    )
    (net (code "56") (name "Net-(D237-A)") (class "Default")
      (node (ref "D237") (pin "1") (pinfunction "A_1") (pintype "passive"))
      (node (ref "S237") (pin "1") (pinfunction "1_1") (pintype "passive"))
    )
    (net (code "57") (name "Net-(D238-A)") (class "Default")
      (node (ref "D238") (pin "1") (pinfunction "A_1") (pintype "passive"))
      (node (ref "S238") (pin "1") (pinfunction "1_1") (pintype "passive"))
    )
    (net (code "58") (name "Net-(D239-A)") (class "Default")
      (node (ref "D239") (pin "1") (pinfunction "A_1") (pintype "passive"))
      (node (ref "S239") (pin "1") (pinfunction "1_1") (pintype "passive"))
    )
    (net (code "59") (name "Net-(D240-A)") (class "Default")
      (node (ref "D240") (pin "1") (pinfunction "A_1") (pintype "passive"))
      (node (ref "S240") (pin "1") (pinfunction "1_1") (pintype "passive"))
    )
    (net (code "60") (name "Net-(D242-A)") (class "Default")
      (node (ref "D242") (pin "1") (pinfunction "A_1") (pintype "passive"))
      (node (ref "S242") (pin "1") (pinfunction "1_1") (pintype "passive"))
    )
    (net (code "61") (name "Net-(D243-A)") (class "Default")
      (node (ref "D243") (pin "1") (pinfunction "A_1") (pintype "passive"))
      (node (ref "S243") (pin "1") (pinfunction "1_1") (pintype "passive"))
    )
    (net (code "62") (name "Net-(D244-A)") (class "Default")
      (node (ref "D244") (pin "1") (pinfunction "A_1") (pintype "passive"))
      (node (ref "S244") (pin "1") (pinfunction "1_1") (pintype "passive"))
    )
    (net (code "63") (name "Net-(D245-A)") (class "Default")
      (node (ref "D245") (pin "1") (pinfunction "A_1") (pintype "passive"))
      (node (ref "S245") (pin "1") (pinfunction "1_1") (pintype "passive"))
    )
    (net (code "64") (name "Net-(D246-A)") (class "Default")
      (node (ref "D246") (pin "1") (pinfunction "A_1") (pintype "passive"))
      (node (ref "S246") (pin "1") (pinfunction "1_1") (pintype "passive"))
    )
    (net (code "65") (name "Net-(D247-A)") (class "Default")
      (node (ref "D247") (pin "1") (pinfunction "A_1") (pintype "passive"))
      (node (ref "S247") (pin "1") (pinfunction "1_1") (pintype "passive"))
    )
    (net (code "66") (name "Net-(D248-A)") (class "Default")
      (node (ref "D248") (pin "1") (pinfunction "A_1") (pintype "passive"))
      (node (ref "S248") (pin "1") (pinfunction "1_1") (pintype "passive"))
    )
    (net (code "67") (name "Net-(D249-A)") (class "Default")
      (node (ref "D249") (pin "1") (pinfunction "A_1") (pintype "passive"))
      (node (ref "S249") (pin "1") (pinfunction "1_1") (pintype "passive"))
    )
    (net (code "68") (name "Net-(D250-A)") (class "Default")
      (node (ref "D250") (pin "1") (pinfunction "A_1") (pintype "passive"))
      (node (ref "S250") (pin "1") (pinfunction "1_1") (pintype "passive"))
    )
    (net (code "69") (name "Net-(D251-A)") (class "Default")
      (node (ref "D251") (pin "1") (pinfunction "A_1") (pintype "passive"))
      (node (ref "S251") (pin "1") (pinfunction "1_1") (pintype "passive"))
    )
    (net (code "70") (name "Net-(D252-A)") (class "Default")
      (node (ref "D252") (pin "1") (pinfunction "A_1") (pintype "passive"))
      (node (ref "S252") (pin "1") (pinfunction "1_1") (pintype "passive"))
    )
    (net (code "71") (name "Net-(D253-A)") (class "Default")
      (node (ref "D253") (pin "1") (pinfunction "A_1") (pintype "passive"))
      (node (ref "S253") (pin "1") (pinfunction "1_1") (pintype "passive"))
    )
    (net (code "72") (name "Net-(D254-A)") (class "Default")
      (node (ref "D254") (pin "1") (pinfunction "A_1") (pintype "passive"))
      (node (ref "S254") (pin "1") (pinfunction "1_1") (pintype "passive"))
    )
    (net (code "73") (name "Net-(D256-A)") (class "Default")
      (node (ref "D256") (pin "1") (pinfunction "A_1") (pintype "passive"))
      (node (ref "S256") (pin "1") (pinfunction "1_1") (pintype "passive"))
    )
    (net (code "74") (name "Net-(D257-A)") (class "Default")
      (node (ref "D257") (pin "1") (pinfunction "A_1") (pintype "passive"))
      (node (ref "S257") (pin "1") (pinfunction "1_1") (pintype "passive"))
    )
    (net (code "75") (name "Net-(D258-A)") (class "Default")
      (node (ref "D258") (pin "1") (pinfunction "A_1") (pintype "passive"))
      (node (ref "S258") (pin "1") (pinfunction "1_1") (pintype "passive"))
    )
    (net (code "76") (name "Net-(D259-A)") (class "Default")
      (node (ref "D259") (pin "1") (pinfunction "A_1") (pintype "passive"))
      (node (ref "S259") (pin "1") (pinfunction "1_1") (pintype "passive"))
    )
    (net (code "77") (name "Net-(D260-A)") (class "Default")
      (node (ref "D260") (pin "1") (pinfunction "A_1") (pintype "passive"))
      (node (ref "S260") (pin "1") (pinfunction "1_1") (pintype "passive"))
    )
    (net (code "78") (name "Net-(D262-A)") (class "Default")
      (node (ref "D262") (pin "1") (pinfunction "A_1") (pintype "passive"))
      (node (ref "S262") (pin "1") (pinfunction "1_1") (pintype "passive"))
    )
    (net (code "79") (name "Net-(D264-A)") (class "Default")
      (node (ref "D264") (pin "1") (pinfunction "A_1") (pintype "passive"))
      (node (ref "S264") (pin "1") (pinfunction "1_1") (pintype "passive"))
    )
    (net (code "80") (name "Net-(D265-A)") (class "Default")
      (node (ref "D265") (pin "1") (pinfunction "A_1") (pintype "passive"))
      (node (ref "S265") (pin "1") (pinfunction "1_1") (pintype "passive"))
    )
    (net (code "81") (name "Net-(D266-A)") (class "Default")
      (node (ref "D266") (pin "1") (pinfunction "A_1") (pintype "passive"))
      (node (ref "S266") (pin "1") (pinfunction "1_1") (pintype "passive"))
    )
    (net (code "82") (name "Net-(D267-A)") (class "Default")
      (node (ref "D267") (pin "1") (pinfunction "A_1") (pintype "passive"))
      (node (ref "S267") (pin "1") (pinfunction "1_1") (pintype "passive"))
    )
    (net (code "83") (name "Net-(D268-A)") (class "Default")
      (node (ref "D268") (pin "1") (pinfunction "A_1") (pintype "passive"))
      (node (ref "S268") (pin "1") (pinfunction "1_1") (pintype "passive"))
    )
    (net (code "84") (name "Net-(D269-A)") (class "Default")
      (node (ref "D269") (pin "1") (pinfunction "A_1") (pintype "passive"))
      (node (ref "S269") (pin "1") (pinfunction "1_1") (pintype "passive"))
    )
    (net (code "85") (name "Net-(D270-A)") (class "Default")
      (node (ref "D270") (pin "1") (pinfunction "A_1") (pintype "passive"))
      (node (ref "S270") (pin "1") (pinfunction "1_1") (pintype "passive"))
    )
  )
)
